# App_Board_V1_31_bottom_labeled.net
KiCad netlist of a schematic drawn in EAGLE
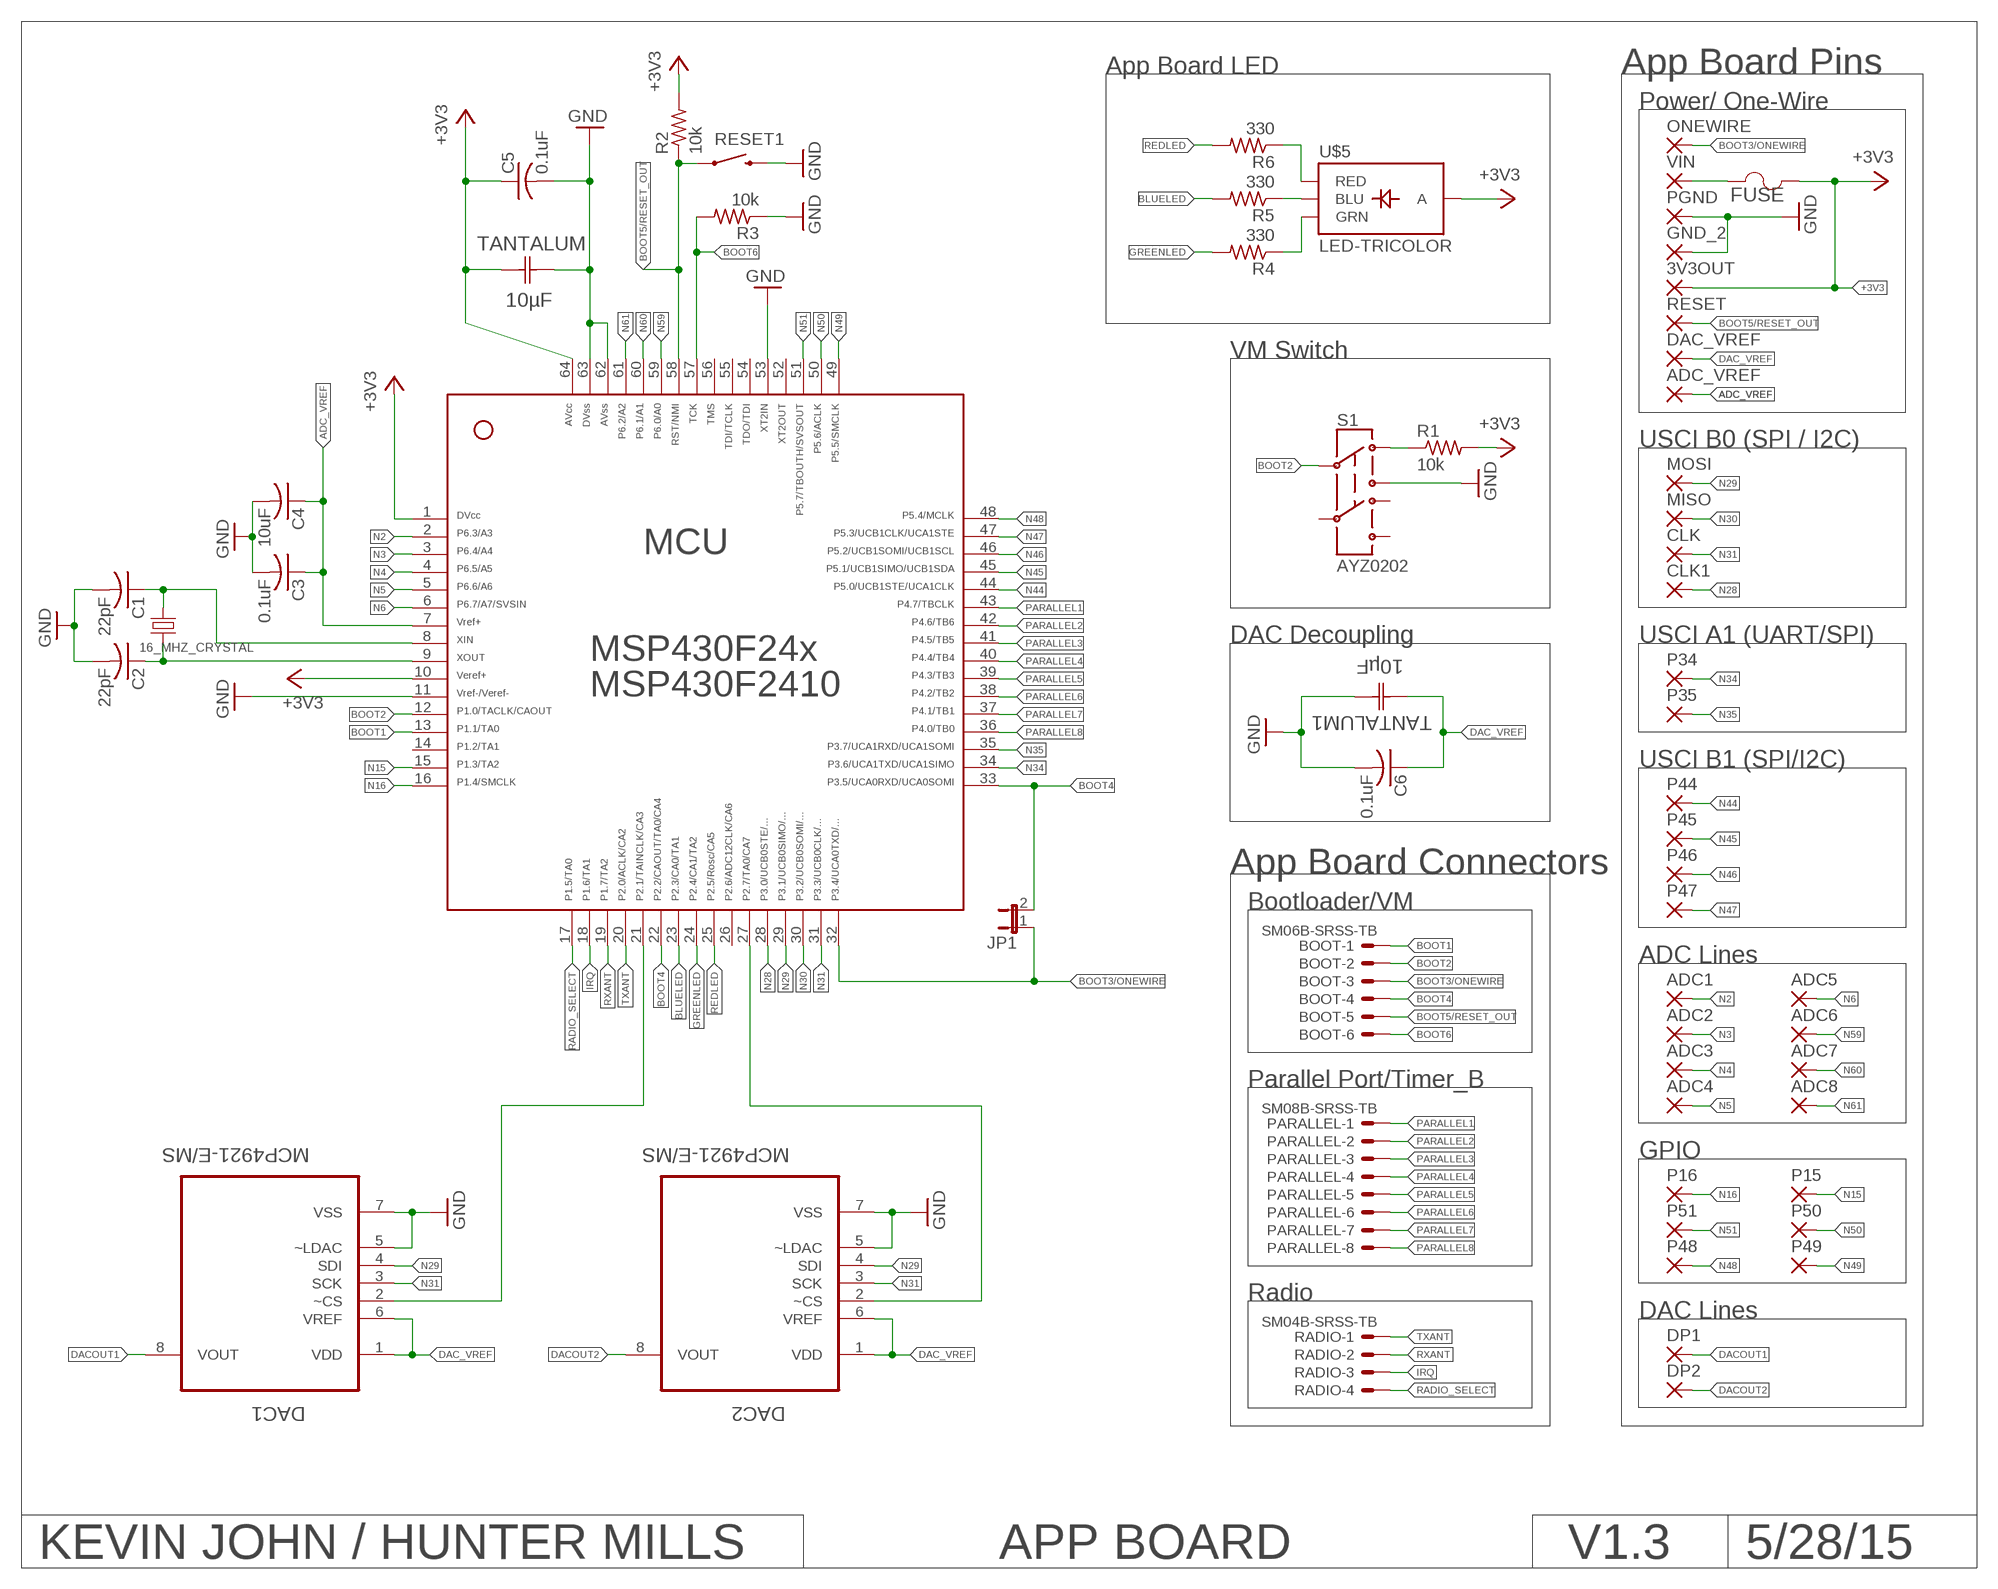
[diagram p0: schematic, sheet 1]

(export (version "E")
  (design (tool "Eeschema 10.0.6"))
  (components
    (comp (ref "3V3OUT")
      (value "1,6/0,9")
      (footprint "eagle-import:1,6_0,9")
      (libsource (lib "eagle-import") (part "1,6/0,9"))
    )
    (comp (ref "16_MHZ_CRYSTAL")
      (value "HUNTERCRYSTAL")
      (footprint "eagle-import:CRYSTAL-SMD-5X3")
      (libsource (lib "eagle-import") (part "HUNTERCRYSTAL"))
    )
    (comp (ref "ADC1")
      (value "1,6/0,9")
      (footprint "eagle-import:1,6_0,9")
      (libsource (lib "eagle-import") (part "1,6/0,9"))
    )
    (comp (ref "ADC2")
      (value "1,6/0,9")
      (footprint "eagle-import:1,6_0,9")
      (libsource (lib "eagle-import") (part "1,6/0,9"))
    )
    (comp (ref "ADC3")
      (value "1,6/0,9")
      (footprint "eagle-import:1,6_0,9")
      (libsource (lib "eagle-import") (part "1,6/0,9"))
    )
    (comp (ref "ADC4")
      (value "1,6/0,9")
      (footprint "eagle-import:1,6_0,9")
      (libsource (lib "eagle-import") (part "1,6/0,9"))
    )
    (comp (ref "ADC5")
      (value "1,6/0,9")
      (footprint "eagle-import:1,6_0,9")
      (libsource (lib "eagle-import") (part "1,6/0,9"))
    )
    (comp (ref "ADC6")
      (value "1,6/0,9")
      (footprint "eagle-import:1,6_0,9")
      (libsource (lib "eagle-import") (part "1,6/0,9"))
    )
    (comp (ref "ADC7")
      (value "1,6/0,9")
      (footprint "eagle-import:1,6_0,9")
      (libsource (lib "eagle-import") (part "1,6/0,9"))
    )
    (comp (ref "ADC8")
      (value "1,6/0,9")
      (footprint "eagle-import:1,6_0,9")
      (libsource (lib "eagle-import") (part "1,6/0,9"))
    )
    (comp (ref "ADC_VREF")
      (value "1,6/0,9")
      (footprint "eagle-import:1,6_0,9")
      (libsource (lib "eagle-import") (part "1,6/0,9"))
    )
    (comp (ref "BOOT")
      (value "SM06B-SRSS-TB")
      (footprint "eagle-import:SM06B-SRSS-TB")
      (libsource (lib "eagle-import") (part "?M06B-SRSS-TBS"))
    )
    (comp (ref "C1")
      (value "22pF")
      (footprint "eagle-import:C0805")
      (libsource (lib "eagle-import") (part "C-USC0805"))
    )
    (comp (ref "C2")
      (value "22pF")
      (footprint "eagle-import:C0805")
      (libsource (lib "eagle-import") (part "C-USC0805"))
    )
    (comp (ref "C3")
      (value "0.1uF")
      (footprint "eagle-import:C0805")
      (libsource (lib "eagle-import") (part "C-USC0805"))
    )
    (comp (ref "C4")
      (value "10uF")
      (footprint "eagle-import:C0805")
      (libsource (lib "eagle-import") (part "C-USC0805"))
    )
    (comp (ref "C5")
      (value "0.1uF")
      (footprint "eagle-import:C0805")
      (libsource (lib "eagle-import") (part "C-USC0805"))
    )
    (comp (ref "C6")
      (value "0.1uF")
      (footprint "eagle-import:C0805")
      (libsource (lib "eagle-import") (part "C-USC0805"))
    )
    (comp (ref "CLK")
      (value "1,6/0,9")
      (footprint "eagle-import:1,6_0,9")
      (libsource (lib "eagle-import") (part "1,6/0,9"))
    )
    (comp (ref "CLK1")
      (value "1,6/0,9")
      (footprint "eagle-import:1,6_0,9")
      (libsource (lib "eagle-import") (part "1,6/0,9"))
    )
    (comp (ref "DAC1")
      (value "MCP4921-E/MS")
      (footprint "eagle-import:SOP65P490X110-8N")
      (libsource (lib "eagle-import") (part "MCP4921-E/MS"))
    )
    (comp (ref "DAC2")
      (value "MCP4921-E/MS")
      (footprint "eagle-import:SOP65P490X110-8N")
      (libsource (lib "eagle-import") (part "MCP4921-E/MS"))
    )
    (comp (ref "DAC_VREF")
      (value "1,6/0,9")
      (footprint "eagle-import:1,6_0,9")
      (libsource (lib "eagle-import") (part "1,6/0,9"))
    )
    (comp (ref "DP1")
      (value "1,6/0,9")
      (footprint "eagle-import:1,6_0,9")
      (libsource (lib "eagle-import") (part "1,6/0,9"))
    )
    (comp (ref "DP2")
      (value "1,6/0,9")
      (footprint "eagle-import:1,6_0,9")
      (libsource (lib "eagle-import") (part "1,6/0,9"))
    )
    (comp (ref "FUSE")
      (value "HUNTERFUSE")
      (footprint "eagle-import:CAPC4532X254N")
      (libsource (lib "eagle-import") (part "HUNTERFUSE"))
    )
    (comp (ref "GND_2")
      (value "1,6/0,9")
      (footprint "eagle-import:1,6_0,9")
      (libsource (lib "eagle-import") (part "1,6/0,9"))
    )
    (comp (ref "JP1")
      (value "JP1E")
      (footprint "eagle-import:JP1")
      (libsource (lib "eagle-import") (part "JP1E"))
    )
    (comp (ref "MCU")
      (value "F24[X/10]---PM64")
      (footprint "eagle-import:PM_PAG64")
      (libsource (lib "eagle-import") (part "F24[X/10]---PM64"))
    )
    (comp (ref "MISO")
      (value "1,6/0,9")
      (footprint "eagle-import:1,6_0,9")
      (libsource (lib "eagle-import") (part "1,6/0,9"))
    )
    (comp (ref "MOSI")
      (value "1,6/0,9")
      (footprint "eagle-import:1,6_0,9")
      (libsource (lib "eagle-import") (part "1,6/0,9"))
    )
    (comp (ref "ONEWIRE")
      (value "1,6/0,9")
      (footprint "eagle-import:1,6_0,9")
      (libsource (lib "eagle-import") (part "1,6/0,9"))
    )
    (comp (ref "P15")
      (value "1,6/0,9")
      (footprint "eagle-import:1,6_0,9")
      (libsource (lib "eagle-import") (part "1,6/0,9"))
    )
    (comp (ref "P16")
      (value "1,6/0,9")
      (footprint "eagle-import:1,6_0,9")
      (libsource (lib "eagle-import") (part "1,6/0,9"))
    )
    (comp (ref "P34")
      (value "1,6/0,9")
      (footprint "eagle-import:1,6_0,9")
      (libsource (lib "eagle-import") (part "1,6/0,9"))
    )
    (comp (ref "P35")
      (value "1,6/0,9")
      (footprint "eagle-import:1,6_0,9")
      (libsource (lib "eagle-import") (part "1,6/0,9"))
    )
    (comp (ref "P44")
      (value "1,6/0,9")
      (footprint "eagle-import:1,6_0,9")
      (libsource (lib "eagle-import") (part "1,6/0,9"))
    )
    (comp (ref "P45")
      (value "1,6/0,9")
      (footprint "eagle-import:1,6_0,9")
      (libsource (lib "eagle-import") (part "1,6/0,9"))
    )
    (comp (ref "P46")
      (value "1,6/0,9")
      (footprint "eagle-import:1,6_0,9")
      (libsource (lib "eagle-import") (part "1,6/0,9"))
    )
    (comp (ref "P47")
      (value "1,6/0,9")
      (footprint "eagle-import:1,6_0,9")
      (libsource (lib "eagle-import") (part "1,6/0,9"))
    )
    (comp (ref "P48")
      (value "1,6/0,9")
      (footprint "eagle-import:1,6_0,9")
      (libsource (lib "eagle-import") (part "1,6/0,9"))
    )
    (comp (ref "P49")
      (value "1,6/0,9")
      (footprint "eagle-import:1,6_0,9")
      (libsource (lib "eagle-import") (part "1,6/0,9"))
    )
    (comp (ref "P50")
      (value "1,6/0,9")
      (footprint "eagle-import:1,6_0,9")
      (libsource (lib "eagle-import") (part "1,6/0,9"))
    )
    (comp (ref "P51")
      (value "1,6/0,9")
      (footprint "eagle-import:1,6_0,9")
      (libsource (lib "eagle-import") (part "1,6/0,9"))
    )
    (comp (ref "PARALLEL")
      (value "SM08B-SRSS-TB")
      (footprint "eagle-import:SM08B-SRSS-TB")
      (libsource (lib "eagle-import") (part "?M08B-SRSS-TBS"))
    )
    (comp (ref "PGND")
      (value "1,6/0,9")
      (footprint "eagle-import:1,6_0,9")
      (libsource (lib "eagle-import") (part "1,6/0,9"))
    )
    (comp (ref "R1")
      (value "10k")
      (footprint "eagle-import:R0603")
      (libsource (lib "eagle-import") (part "R-US_R0603"))
    )
    (comp (ref "R2")
      (value "10k")
      (footprint "eagle-import:R0603")
      (libsource (lib "eagle-import") (part "R-US_R0603"))
    )
    (comp (ref "R3")
      (value "10k")
      (footprint "eagle-import:R0603")
      (libsource (lib "eagle-import") (part "R-US_R0603"))
    )
    (comp (ref "R4")
      (value "330")
      (footprint "eagle-import:R0603")
      (libsource (lib "eagle-import") (part "R-US_R0603"))
    )
    (comp (ref "R5")
      (value "330")
      (footprint "eagle-import:R0603")
      (libsource (lib "eagle-import") (part "R-US_R0603"))
    )
    (comp (ref "R6")
      (value "330")
      (footprint "eagle-import:R0603")
      (libsource (lib "eagle-import") (part "R-US_R0603"))
    )
    (comp (ref "RADIO")
      (value "SM04B-SRSS-TB")
      (footprint "eagle-import:SM04B-SRSS-TB")
      (libsource (lib "eagle-import") (part "?M04B-SRSS-TBS"))
    )
    (comp (ref "RESET")
      (value "1,6/0,9")
      (footprint "eagle-import:1,6_0,9")
      (libsource (lib "eagle-import") (part "1,6/0,9"))
    )
    (comp (ref "RESET1")
      (value "SWITCH-MOMENTARY-2SMD")
      (footprint "eagle-import:TACTILE-SWITCH-SMD")
      (libsource (lib "eagle-import") (part "SWITCH-MOMENTARY-2SMD"))
    )
    (comp (ref "S1")
      (value "AYZ0202")
      (footprint "eagle-import:AYZ0202")
      (libsource (lib "eagle-import") (part "AYZ0202"))
    )
    (comp (ref "TANTALUM")
      (value "10µF")
      (footprint "eagle-import:CAPCP3528X120N")
      (fields (field (name "MPN") "TAJT106K016R"))
      (libsource (lib "eagle-import") (part "TAJT106K016R"))
    )
    (comp (ref "TANTALUM1")
      (value "10µF")
      (footprint "eagle-import:CAPCP3528X120N")
      (fields (field (name "MPN") "TAJT106K016R"))
      (libsource (lib "eagle-import") (part "TAJT106K016R"))
    )
    (comp (ref "U$5")
      (value "LED-TRICOLOR")
      (footprint "eagle-import:LED-TRICOLOR-SMD")
      (libsource (lib "eagle-import") (part "LED-TRICOLOR"))
    )
    (comp (ref "VIN")
      (value "1,6/0,9")
      (footprint "eagle-import:1,6_0,9")
      (libsource (lib "eagle-import") (part "1,6/0,9"))
    )
  )
  (nets
    (net (code "1") (name "+3V3") (class "Default")
      (node (ref "3V3OUT") (pin "1") (pinfunction "P_1") (pintype "passive"))
      (node (ref "C5") (pin "1") (pinfunction "1_1") (pintype "passive"))
      (node (ref "FUSE") (pin "2") (pinfunction "2_2") (pintype "passive"))
      (node (ref "MCU") (pin "1") (pinfunction "1_1") (pintype "power_in"))
      (node (ref "MCU") (pin "10") (pinfunction "10_10") (pintype "output"))
      (node (ref "MCU") (pin "64") (pinfunction "64_64") (pintype "power_in"))
      (node (ref "R1") (pin "2") (pinfunction "2_2") (pintype "passive"))
      (node (ref "R2") (pin "2") (pinfunction "2_2") (pintype "passive"))
      (node (ref "TANTALUM") (pin "1") (pinfunction "C1_1") (pintype "passive"))
      (node (ref "U$5") (pin "A") (pinfunction "A_A") (pintype "bidirectional"))
    )
    (net (code "2") (name "ADC_VREF") (class "Default")
      (node (ref "ADC_VREF") (pin "1") (pinfunction "P_1") (pintype "passive"))
      (node (ref "C3") (pin "1") (pinfunction "1_1") (pintype "passive"))
      (node (ref "C4") (pin "1") (pinfunction "1_1") (pintype "passive"))
      (node (ref "MCU") (pin "7") (pinfunction "7_7") (pintype "output"))
    )
    (net (code "3") (name "BLUELED") (class "Default")
      (node (ref "MCU") (pin "23") (pinfunction "23_23") (pintype "bidirectional"))
      (node (ref "R5") (pin "2") (pinfunction "2_2") (pintype "passive"))
    )
    (net (code "4") (name "BOOT1") (class "Default")
      (node (ref "BOOT") (pin "1") (pinfunction "S_1") (pintype "passive"))
      (node (ref "MCU") (pin "13") (pinfunction "13_13") (pintype "bidirectional"))
    )
    (net (code "5") (name "BOOT2") (class "Default")
      (node (ref "BOOT") (pin "2") (pinfunction "S_2") (pintype "passive"))
      (node (ref "MCU") (pin "12") (pinfunction "12_12") (pintype "bidirectional"))
      (node (ref "S1") (pin "2") (pinfunction "2_2") (pintype "bidirectional"))
    )
    (net (code "6") (name "BOOT3{slash}ONEWIRE") (class "Default")
      (node (ref "BOOT") (pin "3") (pinfunction "S_3") (pintype "passive"))
      (node (ref "JP1") (pin "1") (pinfunction "1_1") (pintype "passive"))
      (node (ref "MCU") (pin "32") (pinfunction "32_32") (pintype "bidirectional"))
      (node (ref "ONEWIRE") (pin "1") (pinfunction "P_1") (pintype "passive"))
    )
    (net (code "7") (name "BOOT4") (class "Default")
      (node (ref "BOOT") (pin "4") (pinfunction "S_4") (pintype "passive"))
      (node (ref "JP1") (pin "2") (pinfunction "2_2") (pintype "passive"))
      (node (ref "MCU") (pin "22") (pinfunction "22_22") (pintype "bidirectional"))
      (node (ref "MCU") (pin "33") (pinfunction "33_33") (pintype "bidirectional"))
    )
    (net (code "8") (name "BOOT5{slash}RESET_OUT") (class "Default")
      (node (ref "BOOT") (pin "5") (pinfunction "S_5") (pintype "passive"))
      (node (ref "MCU") (pin "58") (pinfunction "58_58") (pintype "input"))
      (node (ref "R2") (pin "1") (pinfunction "1_1") (pintype "passive"))
      (node (ref "RESET") (pin "1") (pinfunction "P_1") (pintype "passive"))
      (node (ref "RESET1") (pin "1") (pinfunction "1_1") (pintype "passive"))
    )
    (net (code "9") (name "BOOT6") (class "Default")
      (node (ref "BOOT") (pin "6") (pinfunction "S_6") (pintype "passive"))
      (node (ref "MCU") (pin "57") (pinfunction "57_57") (pintype "input"))
      (node (ref "R3") (pin "2") (pinfunction "2_2") (pintype "passive"))
    )
    (net (code "10") (name "DACOUT1") (class "Default")
      (node (ref "DAC1") (pin "8") (pinfunction "VOUT_8") (pintype "output"))
      (node (ref "DP1") (pin "1") (pinfunction "P_1") (pintype "passive"))
    )
    (net (code "11") (name "DACOUT2") (class "Default")
      (node (ref "DAC2") (pin "8") (pinfunction "VOUT_8") (pintype "output"))
      (node (ref "DP2") (pin "1") (pinfunction "P_1") (pintype "passive"))
    )
    (net (code "12") (name "DAC_VREF") (class "Default")
      (node (ref "C6") (pin "1") (pinfunction "1_1") (pintype "passive"))
      (node (ref "DAC1") (pin "1") (pinfunction "VDD_1") (pintype "power_in"))
      (node (ref "DAC1") (pin "6") (pinfunction "VREF_6") (pintype "input"))
      (node (ref "DAC2") (pin "1") (pinfunction "VDD_1") (pintype "power_in"))
      (node (ref "DAC2") (pin "6") (pinfunction "VREF_6") (pintype "input"))
      (node (ref "DAC_VREF") (pin "1") (pinfunction "P_1") (pintype "passive"))
      (node (ref "TANTALUM1") (pin "1") (pinfunction "C1_1") (pintype "passive"))
    )
    (net (code "13") (name "GND") (class "Default")
      (node (ref "C1") (pin "2") (pinfunction "2_2") (pintype "passive"))
      (node (ref "C2") (pin "2") (pinfunction "2_2") (pintype "passive"))
      (node (ref "C3") (pin "2") (pinfunction "2_2") (pintype "passive"))
      (node (ref "C4") (pin "2") (pinfunction "2_2") (pintype "passive"))
      (node (ref "C5") (pin "2") (pinfunction "2_2") (pintype "passive"))
      (node (ref "C6") (pin "2") (pinfunction "2_2") (pintype "passive"))
      (node (ref "DAC1") (pin "5") (pinfunction "~{LDAC}_5") (pintype "input"))
      (node (ref "DAC1") (pin "7") (pinfunction "VSS_7") (pintype "power_in"))
      (node (ref "DAC2") (pin "5") (pinfunction "~{LDAC}_5") (pintype "input"))
      (node (ref "DAC2") (pin "7") (pinfunction "VSS_7") (pintype "power_in"))
      (node (ref "GND_2") (pin "1") (pinfunction "P_1") (pintype "passive"))
      (node (ref "MCU") (pin "11") (pinfunction "11_11") (pintype "input"))
      (node (ref "MCU") (pin "53") (pinfunction "53_53") (pintype "input"))
      (node (ref "MCU") (pin "62") (pinfunction "62_62") (pintype "power_in"))
      (node (ref "MCU") (pin "63") (pinfunction "63_63") (pintype "power_in"))
      (node (ref "PGND") (pin "1") (pinfunction "P_1") (pintype "passive"))
      (node (ref "R3") (pin "1") (pinfunction "1_1") (pintype "passive"))
      (node (ref "RESET1") (pin "3") (pinfunction "2_3") (pintype "passive"))
      (node (ref "S1") (pin "1") (pinfunction "3_1") (pintype "bidirectional"))
      (node (ref "TANTALUM") (pin "2") (pinfunction "C2_2") (pintype "passive"))
      (node (ref "TANTALUM1") (pin "2") (pinfunction "C2_2") (pintype "passive"))
    )
    (net (code "14") (name "GREENLED") (class "Default")
      (node (ref "MCU") (pin "24") (pinfunction "24_24") (pintype "bidirectional"))
      (node (ref "R4") (pin "2") (pinfunction "2_2") (pintype "passive"))
    )
    (net (code "15") (name "IRQ") (class "Default")
      (node (ref "MCU") (pin "18") (pinfunction "18_18") (pintype "bidirectional"))
      (node (ref "RADIO") (pin "3") (pinfunction "S_3") (pintype "passive"))
    )
    (net (code "16") (name "N2") (class "Default")
      (node (ref "ADC1") (pin "1") (pinfunction "P_1") (pintype "passive"))
      (node (ref "MCU") (pin "2") (pinfunction "2_2") (pintype "bidirectional"))
    )
    (net (code "17") (name "N3") (class "Default")
      (node (ref "ADC2") (pin "1") (pinfunction "P_1") (pintype "passive"))
      (node (ref "MCU") (pin "3") (pinfunction "3_3") (pintype "bidirectional"))
    )
    (net (code "18") (name "N4") (class "Default")
      (node (ref "ADC3") (pin "1") (pinfunction "P_1") (pintype "passive"))
      (node (ref "MCU") (pin "4") (pinfunction "4_4") (pintype "bidirectional"))
    )
    (net (code "19") (name "N5") (class "Default")
      (node (ref "ADC4") (pin "1") (pinfunction "P_1") (pintype "passive"))
      (node (ref "MCU") (pin "5") (pinfunction "5_5") (pintype "bidirectional"))
    )
    (net (code "20") (name "N6") (class "Default")
      (node (ref "ADC5") (pin "1") (pinfunction "P_1") (pintype "passive"))
      (node (ref "MCU") (pin "6") (pinfunction "6_6") (pintype "bidirectional"))
    )
    (net (code "21") (name "N15") (class "Default")
      (node (ref "MCU") (pin "15") (pinfunction "15_15") (pintype "bidirectional"))
      (node (ref "P15") (pin "1") (pinfunction "P_1") (pintype "passive"))
    )
    (net (code "22") (name "N16") (class "Default")
      (node (ref "MCU") (pin "16") (pinfunction "16_16") (pintype "bidirectional"))
      (node (ref "P16") (pin "1") (pinfunction "P_1") (pintype "passive"))
    )
    (net (code "23") (name "N28") (class "Default")
      (node (ref "CLK1") (pin "1") (pinfunction "P_1") (pintype "passive"))
      (node (ref "MCU") (pin "28") (pinfunction "28_28") (pintype "bidirectional"))
    )
    (net (code "24") (name "N29") (class "Default")
      (node (ref "DAC1") (pin "4") (pinfunction "SDI_4") (pintype "input"))
      (node (ref "DAC2") (pin "4") (pinfunction "SDI_4") (pintype "input"))
      (node (ref "MCU") (pin "29") (pinfunction "29_29") (pintype "bidirectional"))
      (node (ref "MOSI") (pin "1") (pinfunction "P_1") (pintype "passive"))
    )
    (net (code "25") (name "N30") (class "Default")
      (node (ref "MCU") (pin "30") (pinfunction "30_30") (pintype "bidirectional"))
      (node (ref "MISO") (pin "1") (pinfunction "P_1") (pintype "passive"))
    )
    (net (code "26") (name "N31") (class "Default")
      (node (ref "CLK") (pin "1") (pinfunction "P_1") (pintype "passive"))
      (node (ref "DAC1") (pin "3") (pinfunction "SCK_3") (pintype "input"))
      (node (ref "DAC2") (pin "3") (pinfunction "SCK_3") (pintype "input"))
      (node (ref "MCU") (pin "31") (pinfunction "31_31") (pintype "bidirectional"))
    )
    (net (code "27") (name "N34") (class "Default")
      (node (ref "MCU") (pin "34") (pinfunction "34_34") (pintype "bidirectional"))
      (node (ref "P34") (pin "1") (pinfunction "P_1") (pintype "passive"))
    )
    (net (code "28") (name "N35") (class "Default")
      (node (ref "MCU") (pin "35") (pinfunction "35_35") (pintype "bidirectional"))
      (node (ref "P35") (pin "1") (pinfunction "P_1") (pintype "passive"))
    )
    (net (code "29") (name "N44") (class "Default")
      (node (ref "MCU") (pin "44") (pinfunction "44_44") (pintype "bidirectional"))
      (node (ref "P44") (pin "1") (pinfunction "P_1") (pintype "passive"))
    )
    (net (code "30") (name "N45") (class "Default")
      (node (ref "MCU") (pin "45") (pinfunction "45_45") (pintype "bidirectional"))
      (node (ref "P45") (pin "1") (pinfunction "P_1") (pintype "passive"))
    )
    (net (code "31") (name "N46") (class "Default")
      (node (ref "MCU") (pin "46") (pinfunction "46_46") (pintype "bidirectional"))
      (node (ref "P46") (pin "1") (pinfunction "P_1") (pintype "passive"))
    )
    (net (code "32") (name "N47") (class "Default")
      (node (ref "MCU") (pin "47") (pinfunction "47_47") (pintype "bidirectional"))
      (node (ref "P47") (pin "1") (pinfunction "P_1") (pintype "passive"))
    )
    (net (code "33") (name "N48") (class "Default")
      (node (ref "MCU") (pin "48") (pinfunction "48_48") (pintype "bidirectional"))
      (node (ref "P48") (pin "1") (pinfunction "P_1") (pintype "passive"))
    )
    (net (code "34") (name "N49") (class "Default")
      (node (ref "MCU") (pin "49") (pinfunction "49_49") (pintype "bidirectional"))
      (node (ref "P49") (pin "1") (pinfunction "P_1") (pintype "passive"))
    )
    (net (code "35") (name "N50") (class "Default")
      (node (ref "MCU") (pin "50") (pinfunction "50_50") (pintype "bidirectional"))
      (node (ref "P50") (pin "1") (pinfunction "P_1") (pintype "passive"))
    )
    (net (code "36") (name "N51") (class "Default")
      (node (ref "MCU") (pin "51") (pinfunction "51_51") (pintype "bidirectional"))
      (node (ref "P51") (pin "1") (pinfunction "P_1") (pintype "passive"))
    )
    (net (code "37") (name "N59") (class "Default")
      (node (ref "ADC6") (pin "1") (pinfunction "P_1") (pintype "passive"))
      (node (ref "MCU") (pin "59") (pinfunction "59_59") (pintype "bidirectional"))
    )
    (net (code "38") (name "N60") (class "Default")
      (node (ref "ADC7") (pin "1") (pinfunction "P_1") (pintype "passive"))
      (node (ref "MCU") (pin "60") (pinfunction "60_60") (pintype "bidirectional"))
    )
    (net (code "39") (name "N61") (class "Default")
      (node (ref "ADC8") (pin "1") (pinfunction "P_1") (pintype "passive"))
      (node (ref "MCU") (pin "61") (pinfunction "61_61") (pintype "bidirectional"))
    )
    (net (code "40") (name "Net-(16_MHZ_CRYSTAL-Pad1)") (class "Default")
      (node (ref "16_MHZ_CRYSTAL") (pin "1") (pinfunction "1_1") (pintype "passive"))
      (node (ref "C2") (pin "1") (pinfunction "1_1") (pintype "passive"))
      (node (ref "MCU") (pin "9") (pinfunction "9_9") (pintype "output"))
    )
    (net (code "41") (name "Net-(16_MHZ_CRYSTAL-Pad3)") (class "Default")
      (node (ref "16_MHZ_CRYSTAL") (pin "3") (pinfunction "3_3") (pintype "passive"))
      (node (ref "C1") (pin "1") (pinfunction "1_1") (pintype "passive"))
      (node (ref "MCU") (pin "8") (pinfunction "8_8") (pintype "input"))
    )
    (net (code "42") (name "Net-(DAC1-~{CS})") (class "Default")
      (node (ref "DAC1") (pin "2") (pinfunction "~{CS}_2") (pintype "input"))
      (node (ref "MCU") (pin "21") (pinfunction "21_21") (pintype "bidirectional"))
    )
    (net (code "43") (name "Net-(DAC2-~{CS})") (class "Default")
      (node (ref "DAC2") (pin "2") (pinfunction "~{CS}_2") (pintype "input"))
      (node (ref "MCU") (pin "27") (pinfunction "27_27") (pintype "bidirectional"))
    )
    (net (code "44") (name "Net-(S1-1)") (class "Default")
      (node (ref "R1") (pin "1") (pinfunction "1_1") (pintype "passive"))
      (node (ref "S1") (pin "3") (pinfunction "1_3") (pintype "bidirectional"))
    )
    (net (code "45") (name "Net-(U$5-BLU)") (class "Default")
      (node (ref "R5") (pin "1") (pinfunction "1_1") (pintype "passive"))
      (node (ref "U$5") (pin "B") (pinfunction "BLU_B") (pintype "bidirectional"))
    )
    (net (code "46") (name "Net-(U$5-GRN)") (class "Default")
      (node (ref "R4") (pin "1") (pinfunction "1_1") (pintype "passive"))
      (node (ref "U$5") (pin "G") (pinfunction "GRN_G") (pintype "bidirectional"))
    )
    (net (code "47") (name "Net-(U$5-RED)") (class "Default")
      (node (ref "R6") (pin "1") (pinfunction "1_1") (pintype "passive"))
      (node (ref "U$5") (pin "R") (pinfunction "RED_R") (pintype "bidirectional"))
    )
    (net (code "48") (name "Net-(VIN-P)") (class "Default")
      (node (ref "FUSE") (pin "1") (pinfunction "1_1") (pintype "passive"))
      (node (ref "VIN") (pin "1") (pinfunction "P_1") (pintype "passive"))
    )
    (net (code "49") (name "PARALLEL1") (class "Default")
      (node (ref "MCU") (pin "43") (pinfunction "43_43") (pintype "bidirectional"))
      (node (ref "PARALLEL") (pin "1") (pinfunction "S_1") (pintype "passive"))
    )
    (net (code "50") (name "PARALLEL2") (class "Default")
      (node (ref "MCU") (pin "42") (pinfunction "42_42") (pintype "bidirectional"))
      (node (ref "PARALLEL") (pin "2") (pinfunction "S_2") (pintype "passive"))
    )
    (net (code "51") (name "PARALLEL3") (class "Default")
      (node (ref "MCU") (pin "41") (pinfunction "41_41") (pintype "bidirectional"))
      (node (ref "PARALLEL") (pin "3") (pinfunction "S_3") (pintype "passive"))
    )
    (net (code "52") (name "PARALLEL4") (class "Default")
      (node (ref "MCU") (pin "40") (pinfunction "40_40") (pintype "bidirectional"))
      (node (ref "PARALLEL") (pin "4") (pinfunction "S_4") (pintype "passive"))
    )
    (net (code "53") (name "PARALLEL5") (class "Default")
      (node (ref "MCU") (pin "39") (pinfunction "39_39") (pintype "bidirectional"))
      (node (ref "PARALLEL") (pin "5") (pinfunction "S_5") (pintype "passive"))
    )
    (net (code "54") (name "PARALLEL6") (class "Default")
      (node (ref "MCU") (pin "38") (pinfunction "38_38") (pintype "bidirectional"))
      (node (ref "PARALLEL") (pin "6") (pinfunction "S_6") (pintype "passive"))
    )
    (net (code "55") (name "PARALLEL7") (class "Default")
      (node (ref "MCU") (pin "37") (pinfunction "37_37") (pintype "bidirectional"))
      (node (ref "PARALLEL") (pin "7") (pinfunction "S_7") (pintype "passive"))
    )
    (net (code "56") (name "PARALLEL8") (class "Default")
      (node (ref "MCU") (pin "36") (pinfunction "36_36") (pintype "bidirectional"))
      (node (ref "PARALLEL") (pin "8") (pinfunction "S_8") (pintype "passive"))
    )
    (net (code "57") (name "RADIO_SELECT") (class "Default")
      (node (ref "MCU") (pin "17") (pinfunction "17_17") (pintype "bidirectional"))
      (node (ref "RADIO") (pin "4") (pinfunction "S_4") (pintype "passive"))
    )
    (net (code "58") (name "REDLED") (class "Default")
      (node (ref "MCU") (pin "25") (pinfunction "25_25") (pintype "bidirectional"))
      (node (ref "R6") (pin "2") (pinfunction "2_2") (pintype "passive"))
    )
    (net (code "59") (name "RXANT") (class "Default")
      (node (ref "MCU") (pin "19") (pinfunction "19_19") (pintype "bidirectional"))
      (node (ref "RADIO") (pin "2") (pinfunction "S_2") (pintype "passive"))
    )
    (net (code "60") (name "TXANT") (class "Default")
      (node (ref "MCU") (pin "20") (pinfunction "20_20") (pintype "bidirectional"))
      (node (ref "RADIO") (pin "1") (pinfunction "S_1") (pintype "passive"))
    )
    (net (code "61") (name "unconnected-(MCU-Pad14)") (class "Default")
      (node (ref "MCU") (pin "14") (pinfunction "14_14") (pintype "bidirectional"))
    )
    (net (code "62") (name "unconnected-(MCU-Pad26)") (class "Default")
      (node (ref "MCU") (pin "26") (pinfunction "26_26") (pintype "bidirectional"))
    )
    (net (code "63") (name "unconnected-(MCU-Pad52)") (class "Default")
      (node (ref "MCU") (pin "52") (pinfunction "52_52") (pintype "output"))
    )
    (net (code "64") (name "unconnected-(MCU-Pad54)") (class "Default")
      (node (ref "MCU") (pin "54") (pinfunction "54_54") (pintype "bidirectional"))
    )
    (net (code "65") (name "unconnected-(MCU-Pad55)") (class "Default")
      (node (ref "MCU") (pin "55") (pinfunction "55_55") (pintype "input"))
    )
    (net (code "66") (name "unconnected-(MCU-Pad56)") (class "Default")
      (node (ref "MCU") (pin "56") (pinfunction "56_56") (pintype "input"))
    )
    (net (code "67") (name "unconnected-(S1-4-Pad6)") (class "Default")
      (node (ref "S1") (pin "6") (pinfunction "4_6") (pintype "bidirectional"))
    )
    (net (code "68") (name "unconnected-(S1-6-Pad4)") (class "Default")
      (node (ref "S1") (pin "4") (pinfunction "6_4") (pintype "bidirectional"))
    )
    (net (code "69") (name "unconnected-(S1-Pad5)") (class "Default")
      (node (ref "S1") (pin "5") (pinfunction "5_5") (pintype "bidirectional"))
    )
  )
)
